# SCH_Workshop-components_2025-10-19.net
KiCad netlist of a schematic drawn in EasyEDA
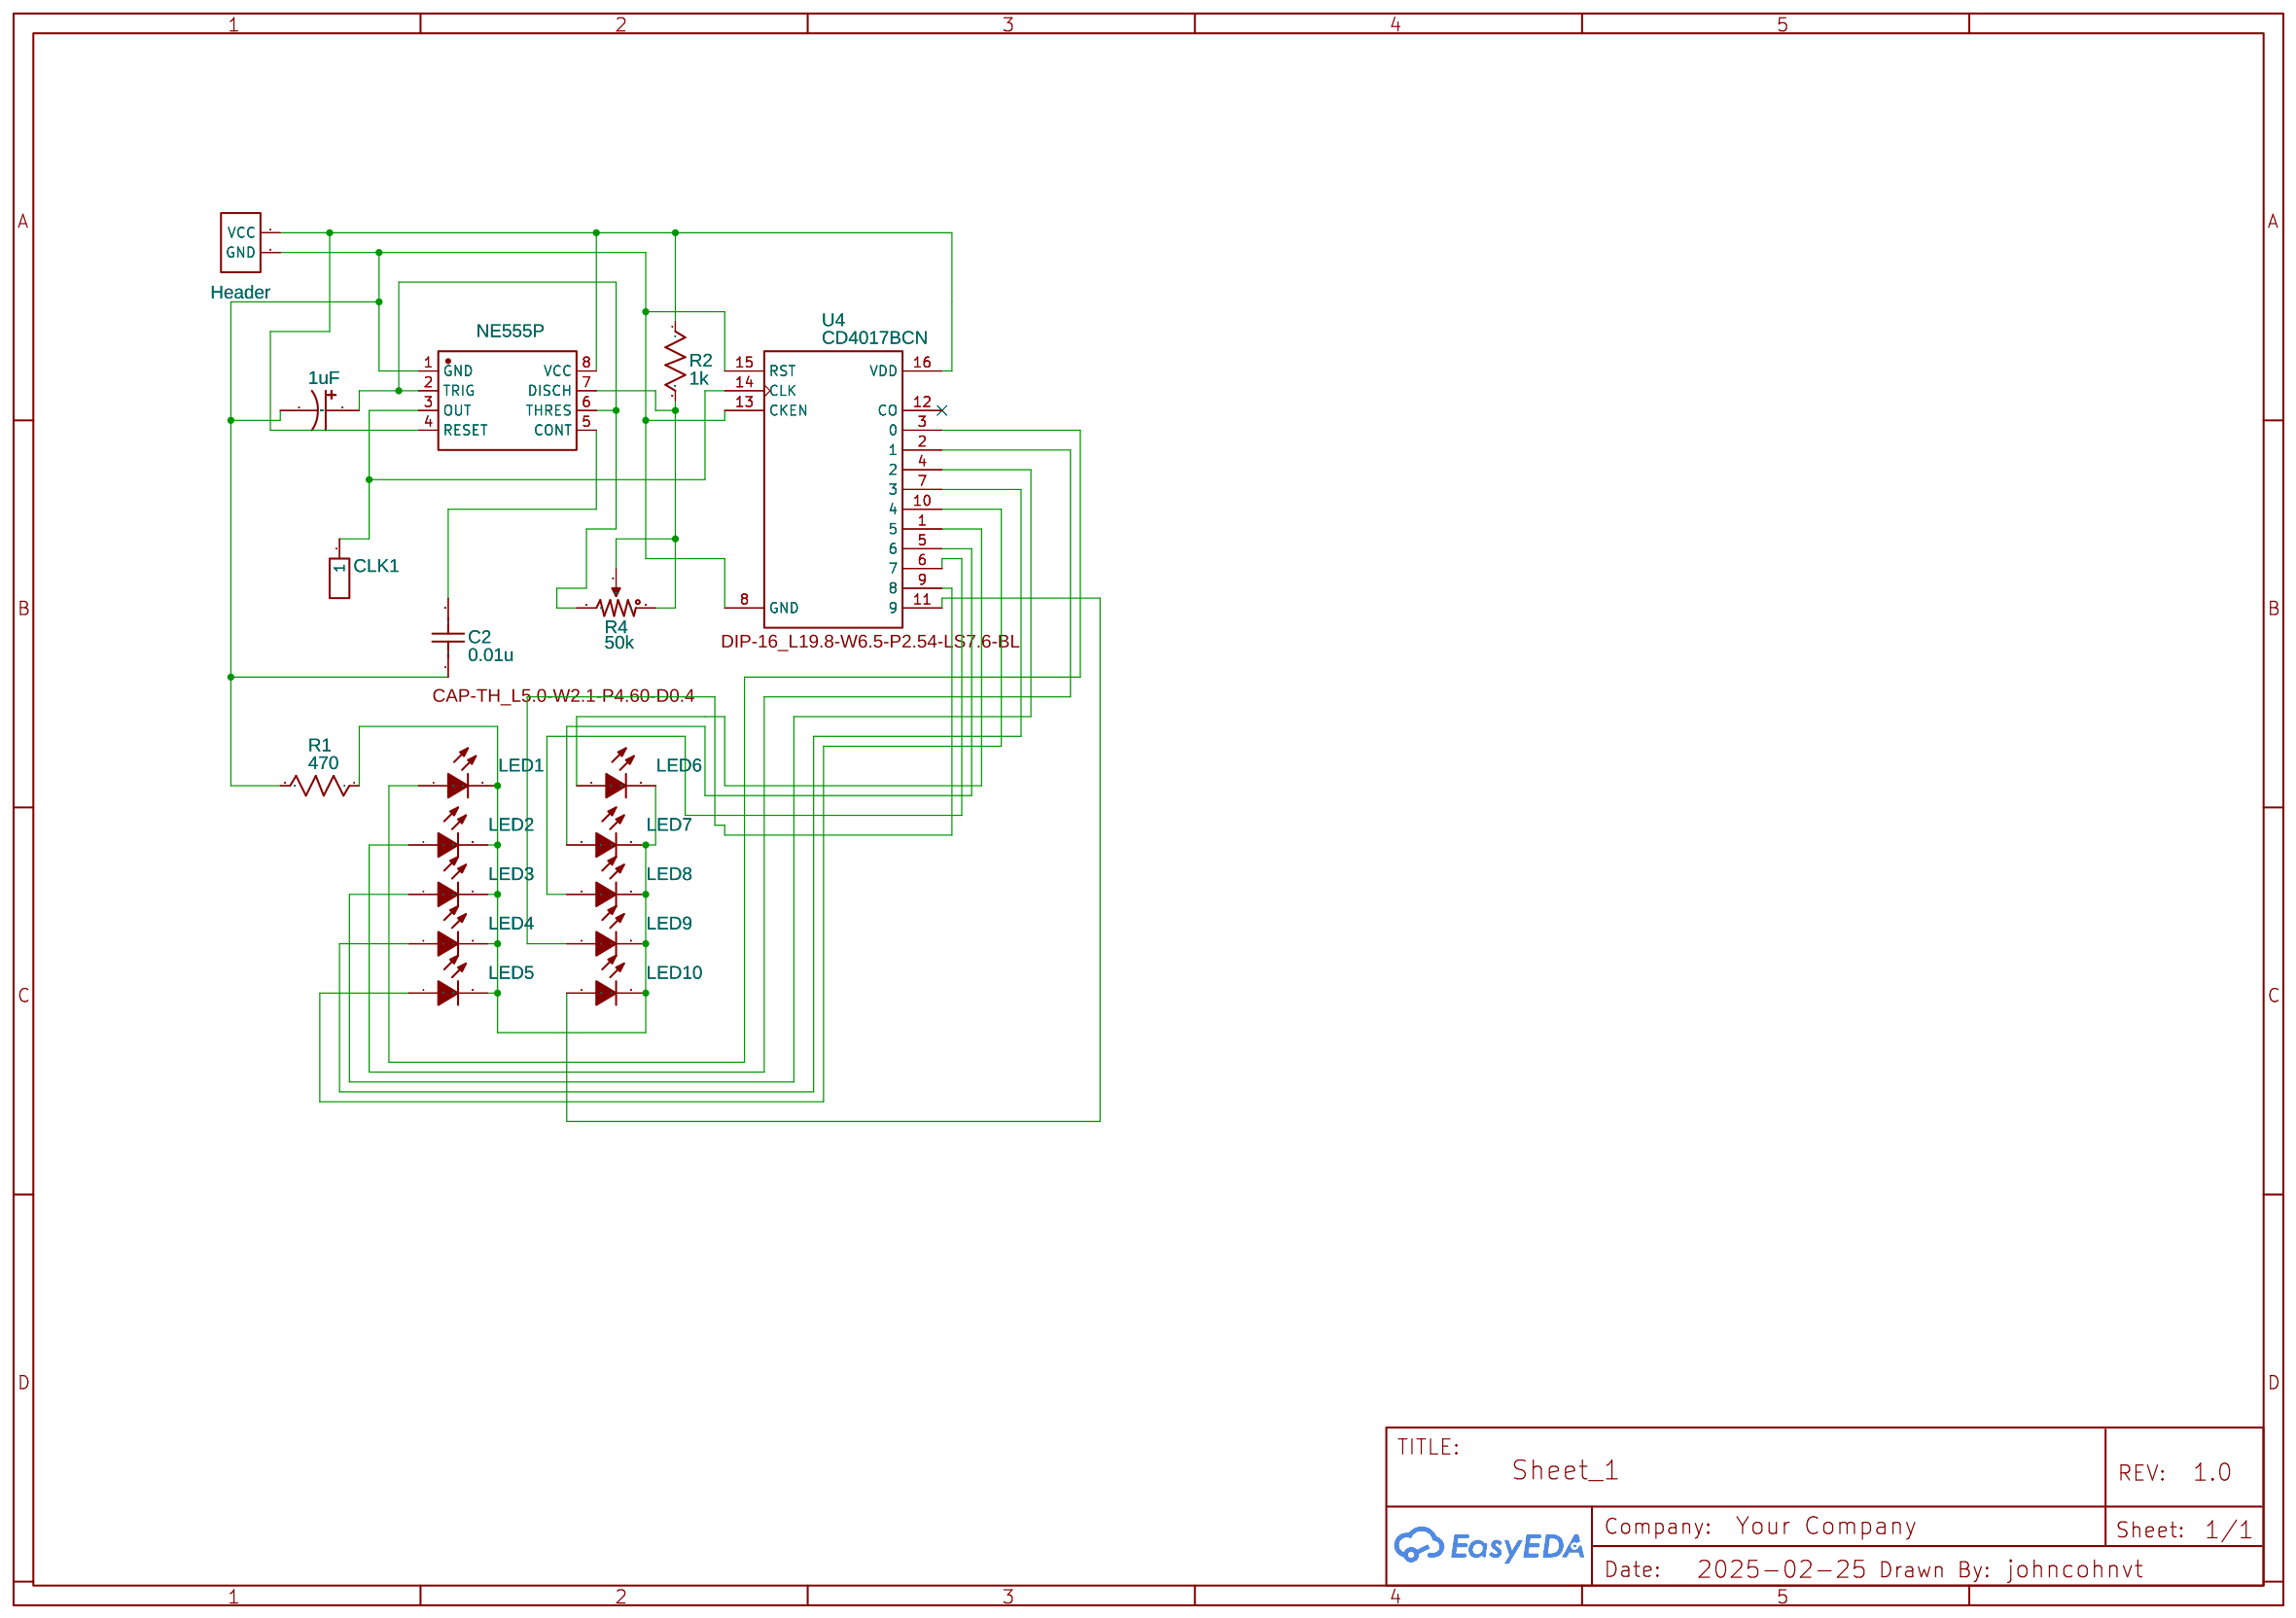
[diagram p0: schematic sheet]

(export (version "E")
  (design (tool "Eeschema 10.0.6"))
  (components
    (comp (ref "C1")
      (value "1uF")
      (fields (field (name "Manufacturer Part") "UVZ1H010MDD") (field (name "Manufacturer") "Nichicon(尼吉康)"))
      (libsource (lib "") (part "UVZ1H010MDD"))
    )
    (comp (ref "C2") (value "0.01u") (libsource (lib "") (part "C_0603_US")))
    (comp (ref "CLK1")
      (value "C81276")
      (fields
        (field (name "Manufacturer Part") "2.54-1*1P针")
        (field (name "Manufacturer") "BOOMELE(Boom Precision Elec)")
      )
      (libsource (lib "") (part "Header-Male-2.54_1x1"))
    )
    (comp (ref "H1") (value "Header") (libsource (lib "") (part "HEADER-FEMALE-2.54_1X2")))
    (comp (ref "LED1") (value "LED_5MM") (libsource (lib "") (part "LED_5MM")))
    (comp (ref "LED2") (value "LED_5MM") (libsource (lib "") (part "LED_5MM")))
    (comp (ref "LED3") (value "LED_5MM") (libsource (lib "") (part "LED_5MM")))
    (comp (ref "LED4") (value "LED_5MM") (libsource (lib "") (part "LED_5MM")))
    (comp (ref "LED5") (value "LED_5MM") (libsource (lib "") (part "LED_5MM")))
    (comp (ref "LED6") (value "LED_5MM") (libsource (lib "") (part "LED_5MM")))
    (comp (ref "LED7") (value "LED_5MM") (libsource (lib "") (part "LED_5MM")))
    (comp (ref "LED8") (value "LED_5MM") (libsource (lib "") (part "LED_5MM")))
    (comp (ref "LED9") (value "LED_5MM") (libsource (lib "") (part "LED_5MM")))
    (comp (ref "LED10") (value "LED_5MM") (libsource (lib "") (part "LED_5MM")))
    (comp (ref "R1")
      (value "470")
      (fields (field (name "Manufacturer Part") "?"))
      (libsource (lib "") (part "Resistor_1"))
    )
    (comp (ref "R2")
      (value "1k")
      (fields (field (name "Manufacturer Part") "?"))
      (libsource (lib "") (part "Resistor"))
    )
    (comp (ref "R4")
      (value "50k")
      (fields (field (name "Manufacturer Part") "?"))
      (libsource (lib "") (part "Potentiometer"))
    )
    (comp (ref "U2")
      (value "NE555P")
      (fields (field (name "Manufacturer") "TI(德州仪器)"))
      (libsource (lib "") (part "NE555P"))
    )
    (comp (ref "U4") (value "CD4017BCN") (libsource (lib "") (part "CD4017BCN")))
  )
  (nets
    (net (code "1") (name "Net-(H1-GND)") (class "Default")
      (node (ref "C1") (pin "2") (pinfunction "2_2") (pintype "unspecified"))
      (node (ref "C2") (pin "1") (pinfunction "1_1") (pintype "unspecified"))
      (node (ref "H1") (pin "2") (pinfunction "GND_2") (pintype "unspecified"))
      (node (ref "R1") (pin "2") (pinfunction "2_2") (pintype "unspecified"))
      (node (ref "U2") (pin "1") (pinfunction "GND_1") (pintype "unspecified"))
      (node (ref "U4") (pin "13") (pinfunction "CKEN_13") (pintype "unspecified"))
      (node (ref "U4") (pin "15") (pinfunction "RST_15") (pintype "unspecified"))
      (node (ref "U4") (pin "8") (pinfunction "GND_8") (pintype "passive"))
    )
    (net (code "2") (name "Net-(H1-VCC)") (class "Default")
      (node (ref "H1") (pin "1") (pinfunction "VCC_1") (pintype "unspecified"))
      (node (ref "R2") (pin "1") (pinfunction "1_1") (pintype "unspecified"))
      (node (ref "U2") (pin "4") (pinfunction "RESET_4") (pintype "unspecified"))
      (node (ref "U2") (pin "8") (pinfunction "VCC_8") (pintype "unspecified"))
      (node (ref "U4") (pin "16") (pinfunction "VDD_16") (pintype "passive"))
    )
    (net (code "3") (name "Net-(LED1-A)") (class "Default")
      (node (ref "LED1") (pin "1") (pinfunction "A_1") (pintype "input"))
      (node (ref "U4") (pin "3") (pinfunction "0_3") (pintype "output"))
    )
    (net (code "4") (name "Net-(LED1-K)") (class "Default")
      (node (ref "LED1") (pin "2") (pinfunction "K_2") (pintype "input"))
      (node (ref "LED10") (pin "2") (pinfunction "K_2") (pintype "input"))
      (node (ref "LED2") (pin "2") (pinfunction "K_2") (pintype "input"))
      (node (ref "LED3") (pin "2") (pinfunction "K_2") (pintype "input"))
      (node (ref "LED4") (pin "2") (pinfunction "K_2") (pintype "input"))
      (node (ref "LED5") (pin "2") (pinfunction "K_2") (pintype "input"))
      (node (ref "LED6") (pin "2") (pinfunction "K_2") (pintype "input"))
      (node (ref "LED7") (pin "2") (pinfunction "K_2") (pintype "input"))
      (node (ref "LED8") (pin "2") (pinfunction "K_2") (pintype "input"))
      (node (ref "LED9") (pin "2") (pinfunction "K_2") (pintype "input"))
      (node (ref "R1") (pin "1") (pinfunction "1_1") (pintype "unspecified"))
    )
    (net (code "5") (name "Net-(LED2-A)") (class "Default")
      (node (ref "LED2") (pin "1") (pinfunction "A_1") (pintype "input"))
      (node (ref "U4") (pin "2") (pinfunction "1_2") (pintype "output"))
    )
    (net (code "6") (name "Net-(LED3-A)") (class "Default")
      (node (ref "LED3") (pin "1") (pinfunction "A_1") (pintype "input"))
      (node (ref "U4") (pin "4") (pinfunction "2_4") (pintype "output"))
    )
    (net (code "7") (name "Net-(LED4-A)") (class "Default")
      (node (ref "LED4") (pin "1") (pinfunction "A_1") (pintype "input"))
      (node (ref "U4") (pin "7") (pinfunction "3_7") (pintype "output"))
    )
    (net (code "8") (name "Net-(LED5-A)") (class "Default")
      (node (ref "LED5") (pin "1") (pinfunction "A_1") (pintype "input"))
      (node (ref "U4") (pin "10") (pinfunction "4_10") (pintype "output"))
    )
    (net (code "9") (name "Net-(LED6-A)") (class "Default")
      (node (ref "LED6") (pin "1") (pinfunction "A_1") (pintype "input"))
      (node (ref "U4") (pin "1") (pinfunction "5_1") (pintype "output"))
    )
    (net (code "10") (name "Net-(LED7-A)") (class "Default")
      (node (ref "LED7") (pin "1") (pinfunction "A_1") (pintype "input"))
      (node (ref "U4") (pin "5") (pinfunction "6_5") (pintype "output"))
    )
    (net (code "11") (name "Net-(LED8-A)") (class "Default")
      (node (ref "LED8") (pin "1") (pinfunction "A_1") (pintype "input"))
      (node (ref "U4") (pin "6") (pinfunction "7_6") (pintype "output"))
    )
    (net (code "12") (name "Net-(LED9-A)") (class "Default")
      (node (ref "LED9") (pin "1") (pinfunction "A_1") (pintype "input"))
      (node (ref "U4") (pin "9") (pinfunction "8_9") (pintype "output"))
    )
    (net (code "13") (name "Net-(LED10-A)") (class "Default")
      (node (ref "LED10") (pin "1") (pinfunction "A_1") (pintype "input"))
      (node (ref "U4") (pin "11") (pinfunction "9_11") (pintype "output"))
    )
    (net (code "14") (name "Net-(R4-2)") (class "Default")
      (node (ref "R2") (pin "2") (pinfunction "2_2") (pintype "unspecified"))
      (node (ref "R4") (pin "2") (pinfunction "3_2") (pintype "unspecified"))
      (node (ref "R4") (pin "3") (pinfunction "2_3") (pintype "unspecified"))
      (node (ref "U2") (pin "7") (pinfunction "DISCH_7") (pintype "unspecified"))
    )
    (net (code "15") (name "Net-(U2-CONT)") (class "Default")
      (node (ref "C2") (pin "2") (pinfunction "2_2") (pintype "unspecified"))
      (node (ref "U2") (pin "5") (pinfunction "CONT_5") (pintype "unspecified"))
    )
    (net (code "16") (name "Net-(U2-OUT)") (class "Default")
      (node (ref "CLK1") (pin "1") (pinfunction "1_1") (pintype "unspecified"))
      (node (ref "U2") (pin "3") (pinfunction "OUT_3") (pintype "unspecified"))
      (node (ref "U4") (pin "14") (pinfunction "CLK_14") (pintype "unspecified"))
    )
    (net (code "17") (name "Net-(U2-THRES)") (class "Default")
      (node (ref "C1") (pin "1") (pinfunction "1_1") (pintype "unspecified"))
      (node (ref "R4") (pin "1") (pinfunction "1_1") (pintype "unspecified"))
      (node (ref "U2") (pin "2") (pinfunction "TRIG_2") (pintype "unspecified"))
      (node (ref "U2") (pin "6") (pinfunction "THRES_6") (pintype "unspecified"))
    )
    (net (code "18") (name "unconnected-(U4-CO-Pad12)") (class "Default")
      (node (ref "U4") (pin "12") (pinfunction "CO_12") (pintype "output+no_connect"))
    )
  )
)
